# VEML6070-Breakout_v10.net
KiCad netlist of a schematic drawn in EAGLE
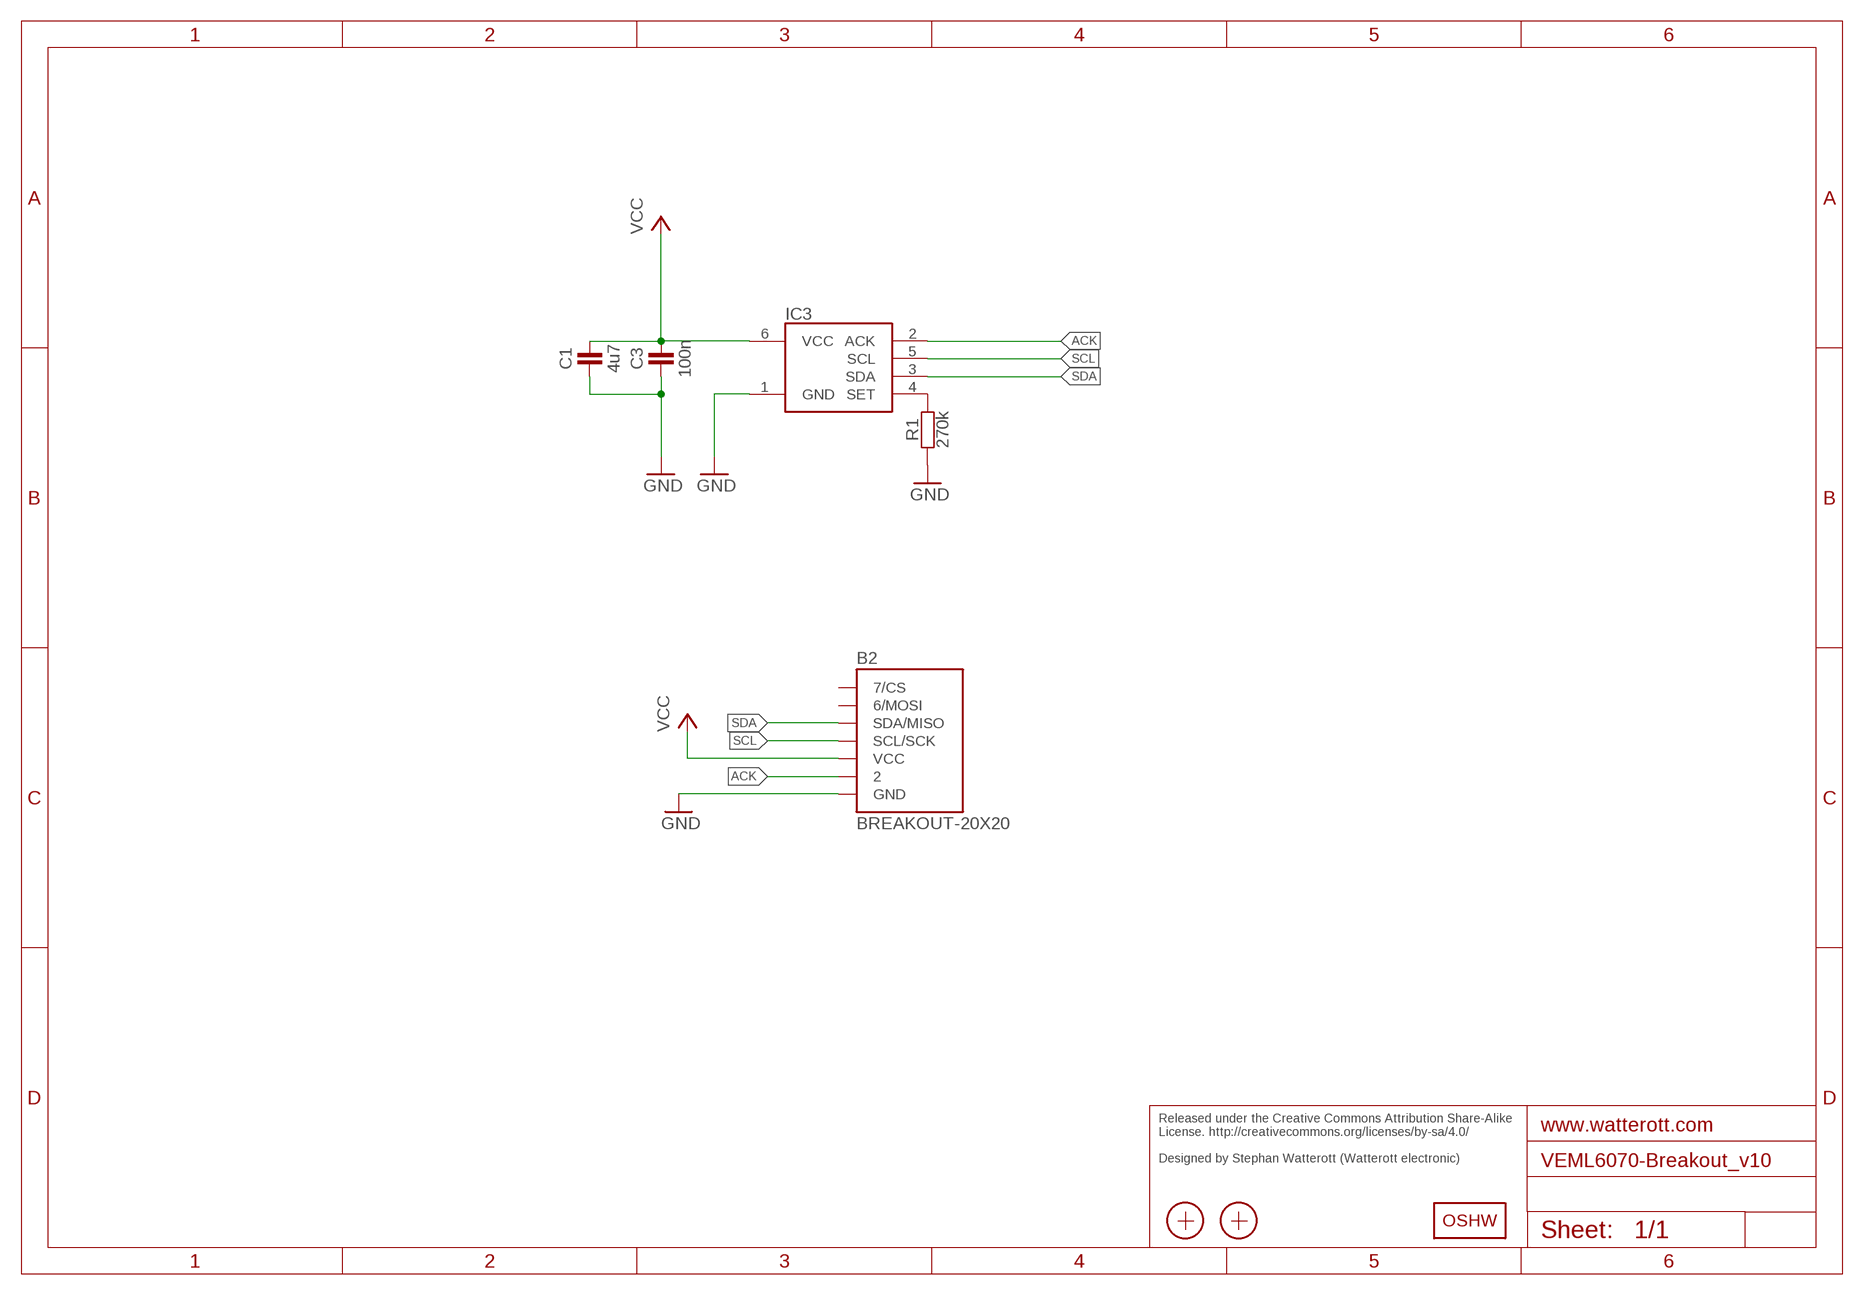
[diagram p0: schematic, sheet 1]

(export (version "E")
  (design (tool "Eeschema 10.0.6"))
  (components
    (comp (ref "B2")
      (value "BREAKOUT-20X20")
      (footprint "eagle-import:BREAKOUT-20X20")
      (libsource (lib "eagle-import") (part "BREAKOUT-20X20"))
    )
    (comp (ref "C1")
      (value "4u7")
      (footprint "eagle-import:R0402")
      (libsource (lib "eagle-import") (part "CAPACITOR-C0402"))
    )
    (comp (ref "C3")
      (value "100n")
      (footprint "eagle-import:R0402")
      (libsource (lib "eagle-import") (part "CAPACITOR-C0402"))
    )
    (comp (ref "IC3")
      (value "VEML6070")
      (footprint "eagle-import:OPLGA")
      (libsource (lib "eagle-import") (part "VEML6070"))
    )
    (comp (ref "LOGO2")
      (value "OSHW_LOGOX0070")
      (footprint "eagle-import:OSHW_6X70")
      (libsource (lib "eagle-import") (part "OSHW_LOGOX0070"))
    )
    (comp (ref "R1")
      (value "270k")
      (footprint "eagle-import:R0402")
      (libsource (lib "eagle-import") (part "RESISTOR-R0402"))
    )
    (comp (ref "X1")
      (value "PASSER-07")
      (footprint "eagle-import:PASSER_07MM")
      (libsource (lib "eagle-import") (part "PASSER-07"))
    )
    (comp (ref "X2")
      (value "PASSER-07")
      (footprint "eagle-import:PASSER_07MM")
      (libsource (lib "eagle-import") (part "PASSER-07"))
    )
  )
  (nets
    (net (code "1") (name "ACK") (class "Default")
      (node (ref "B2") (pin "2") (pinfunction "2_2") (pintype "bidirectional"))
      (node (ref "IC3") (pin "2") (pinfunction "ACK_2") (pintype "output"))
    )
    (net (code "2") (name "GND") (class "Default")
      (node (ref "B2") (pin "GND") (pinfunction "GND_GND") (pintype "power_in"))
      (node (ref "C1") (pin "1") (pinfunction "1_1") (pintype "passive"))
      (node (ref "C3") (pin "1") (pinfunction "1_1") (pintype "passive"))
      (node (ref "IC3") (pin "1") (pinfunction "GND_1") (pintype "power_in"))
      (node (ref "R1") (pin "1") (pinfunction "1_1") (pintype "passive"))
    )
    (net (code "3") (name "Net-(IC3-SET)") (class "Default")
      (node (ref "IC3") (pin "4") (pinfunction "SET_4") (pintype "bidirectional"))
      (node (ref "R1") (pin "2") (pinfunction "2_2") (pintype "passive"))
    )
    (net (code "4") (name "SCL") (class "Default")
      (node (ref "B2") (pin "SCL/SCK") (pinfunction "SCL/SCK_SCL/SCK") (pintype "bidirectional"))
      (node (ref "IC3") (pin "5") (pinfunction "SCL_5") (pintype "input"))
    )
    (net (code "5") (name "SDA") (class "Default")
      (node (ref "B2") (pin "SDA/MISO") (pinfunction "SDA/MISO_SDA/MISO") (pintype "bidirectional"))
      (node (ref "IC3") (pin "3") (pinfunction "SDA_3") (pintype "bidirectional"))
    )
    (net (code "6") (name "VCC") (class "Default")
      (node (ref "B2") (pin "VCC") (pinfunction "VCC_VCC") (pintype "power_in"))
      (node (ref "C1") (pin "2") (pinfunction "2_2") (pintype "passive"))
      (node (ref "C3") (pin "2") (pinfunction "2_2") (pintype "passive"))
      (node (ref "IC3") (pin "6") (pinfunction "VCC_6") (pintype "power_in"))
    )
    (net (code "7") (name "unconnected-(B2-6{slash}MOSI-PadMOSI)") (class "Default")
      (node (ref "B2") (pin "MOSI") (pinfunction "6/MOSI_MOSI") (pintype "bidirectional"))
    )
    (net (code "8") (name "unconnected-(B2-7{slash}CS-PadCS)") (class "Default")
      (node (ref "B2") (pin "CS") (pinfunction "7/CS_CS") (pintype "bidirectional"))
    )
  )
)
